# Baseboard_XIAO.net
KiCad netlist of a schematic drawn in EAGLE
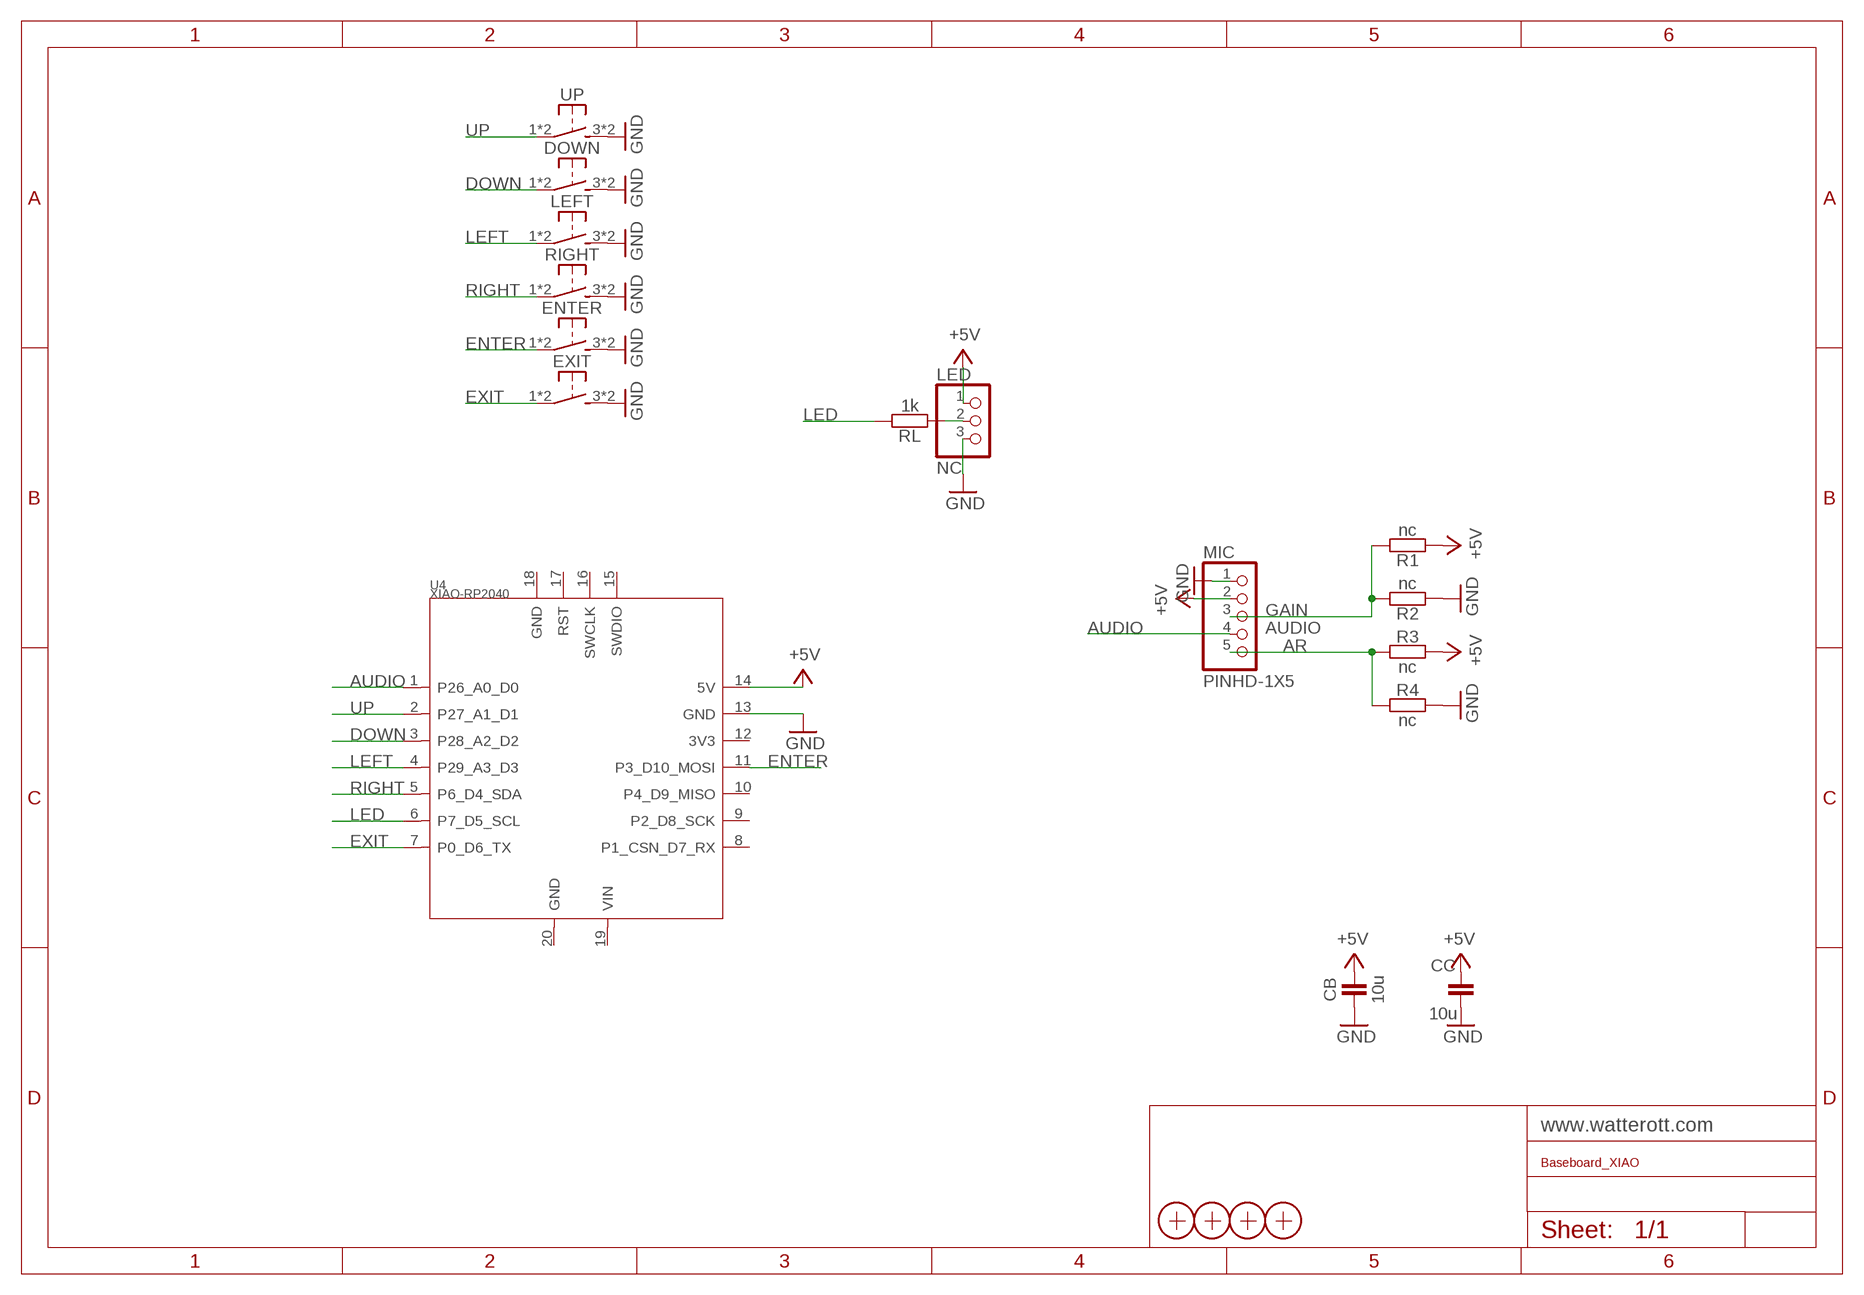
[diagram p0: schematic, sheet 1]

(export (version "E")
  (design (tool "Eeschema 10.0.6"))
  (components
    (comp (ref "CB")
      (value "10u")
      (footprint "eagle-import:C0603")
      (libsource (lib "eagle-import") (part "CAPACITOR-0603"))
    )
    (comp (ref "CC")
      (value "10u")
      (footprint "eagle-import:C0603")
      (libsource (lib "eagle-import") (part "CAPACITOR-0603"))
    )
    (comp (ref "DOWN")
      (value "SW-TACTILELSH")
      (footprint "eagle-import:SW6XG_LSH")
      (libsource (lib "eagle-import") (part "SW-TACTILELSH"))
    )
    (comp (ref "ENTER")
      (value "SW-TACTILELSH")
      (footprint "eagle-import:SW6XG_LSH")
      (libsource (lib "eagle-import") (part "SW-TACTILELSH"))
    )
    (comp (ref "EXIT")
      (value "SW-TACTILELSH")
      (footprint "eagle-import:SW6XG_LSH")
      (libsource (lib "eagle-import") (part "SW-TACTILELSH"))
    )
    (comp (ref "LED")
      (value "NC")
      (footprint "eagle-import:1X03")
      (libsource (lib "eagle-import") (part "PINHD-1X3"))
    )
    (comp (ref "LEFT")
      (value "SW-TACTILELSH")
      (footprint "eagle-import:SW6XG_LSH")
      (libsource (lib "eagle-import") (part "SW-TACTILELSH"))
    )
    (comp (ref "MIC")
      (value "PINHD-1X5")
      (footprint "eagle-import:1X05")
      (libsource (lib "eagle-import") (part "PINHD-1X5"))
    )
    (comp (ref "R1")
      (value "nc")
      (footprint "eagle-import:C0603")
      (libsource (lib "eagle-import") (part "RESISTOR-0603"))
    )
    (comp (ref "R2")
      (value "nc")
      (footprint "eagle-import:C0603")
      (libsource (lib "eagle-import") (part "RESISTOR-0603"))
    )
    (comp (ref "R3")
      (value "nc")
      (footprint "eagle-import:C0603")
      (libsource (lib "eagle-import") (part "RESISTOR-0603"))
    )
    (comp (ref "R4")
      (value "nc")
      (footprint "eagle-import:C0603")
      (libsource (lib "eagle-import") (part "RESISTOR-0603"))
    )
    (comp (ref "RIGHT")
      (value "SW-TACTILELSH")
      (footprint "eagle-import:SW6XG_LSH")
      (libsource (lib "eagle-import") (part "SW-TACTILELSH"))
    )
    (comp (ref "RL")
      (value "1k")
      (footprint "eagle-import:C0603")
      (libsource (lib "eagle-import") (part "RESISTOR-0603"))
    )
    (comp (ref "U4")
      (value "XIAO-RP2040")
      (footprint "eagle-import:XIAO-SAMD21_RP2040-MODULE14P-2.54-21X17.8MM")
      (libsource (lib "eagle-import") (part "XIAO-RP2040"))
    )
    (comp (ref "UP")
      (value "SW-TACTILELSH")
      (footprint "eagle-import:SW6XG_LSH")
      (libsource (lib "eagle-import") (part "SW-TACTILELSH"))
    )
    (comp (ref "X1")
      (value "PASSER-07")
      (footprint "eagle-import:PASSER_07MM")
      (libsource (lib "eagle-import") (part "PASSER-07"))
    )
    (comp (ref "X2")
      (value "PASSER-07")
      (footprint "eagle-import:PASSER_07MM")
      (libsource (lib "eagle-import") (part "PASSER-07"))
    )
    (comp (ref "X3")
      (value "PASSER-07")
      (footprint "eagle-import:PASSER_07MM")
      (libsource (lib "eagle-import") (part "PASSER-07"))
    )
    (comp (ref "X4")
      (value "PASSER-07")
      (footprint "eagle-import:PASSER_07MM")
      (libsource (lib "eagle-import") (part "PASSER-07"))
    )
  )
  (nets
    (net (code "1") (name "+5V") (class "Default")
      (node (ref "CB") (pin "2") (pinfunction "2_2") (pintype "passive"))
      (node (ref "CC") (pin "2") (pinfunction "2_2") (pintype "passive"))
      (node (ref "LED") (pin "1") (pinfunction "1_1") (pintype "passive"))
      (node (ref "MIC") (pin "2") (pinfunction "2_2") (pintype "passive"))
      (node (ref "R1") (pin "1") (pinfunction "1_1") (pintype "passive"))
      (node (ref "R3") (pin "2") (pinfunction "2_2") (pintype "passive"))
      (node (ref "U4") (pin "14") (pinfunction "5V_14") (pintype "bidirectional"))
    )
    (net (code "2") (name "/AR") (class "Default")
      (node (ref "MIC") (pin "5") (pinfunction "5_5") (pintype "passive"))
      (node (ref "R3") (pin "1") (pinfunction "1_1") (pintype "passive"))
      (node (ref "R4") (pin "1") (pinfunction "1_1") (pintype "passive"))
    )
    (net (code "3") (name "/AUDIO") (class "Default")
      (node (ref "MIC") (pin "4") (pinfunction "4_4") (pintype "passive"))
      (node (ref "U4") (pin "1") (pinfunction "P26_A0_D0_1") (pintype "bidirectional"))
    )
    (net (code "4") (name "/DOWN") (class "Default")
      (node (ref "DOWN") (pin "1") (pinfunction "P1_1") (pintype "passive"))
      (node (ref "DOWN") (pin "2") (pinfunction "P1_2") (pintype "passive"))
      (node (ref "U4") (pin "3") (pinfunction "P28_A2_D2_3") (pintype "bidirectional"))
    )
    (net (code "5") (name "/ENTER") (class "Default")
      (node (ref "ENTER") (pin "1") (pinfunction "P1_1") (pintype "passive"))
      (node (ref "ENTER") (pin "2") (pinfunction "P1_2") (pintype "passive"))
      (node (ref "U4") (pin "11") (pinfunction "P3_D10_MOSI_11") (pintype "bidirectional"))
    )
    (net (code "6") (name "/EXIT") (class "Default")
      (node (ref "EXIT") (pin "1") (pinfunction "P1_1") (pintype "passive"))
      (node (ref "EXIT") (pin "2") (pinfunction "P1_2") (pintype "passive"))
      (node (ref "U4") (pin "7") (pinfunction "P0_D6_TX_7") (pintype "bidirectional"))
    )
    (net (code "7") (name "/GAIN") (class "Default")
      (node (ref "MIC") (pin "3") (pinfunction "3_3") (pintype "passive"))
      (node (ref "R1") (pin "2") (pinfunction "2_2") (pintype "passive"))
      (node (ref "R2") (pin "2") (pinfunction "2_2") (pintype "passive"))
    )
    (net (code "8") (name "/LED") (class "Default")
      (node (ref "RL") (pin "2") (pinfunction "2_2") (pintype "passive"))
      (node (ref "U4") (pin "6") (pinfunction "P7_D5_SCL_6") (pintype "bidirectional"))
    )
    (net (code "9") (name "/LEFT") (class "Default")
      (node (ref "LEFT") (pin "1") (pinfunction "P1_1") (pintype "passive"))
      (node (ref "LEFT") (pin "2") (pinfunction "P1_2") (pintype "passive"))
      (node (ref "U4") (pin "4") (pinfunction "P29_A3_D3_4") (pintype "bidirectional"))
    )
    (net (code "10") (name "/RIGHT") (class "Default")
      (node (ref "RIGHT") (pin "1") (pinfunction "P1_1") (pintype "passive"))
      (node (ref "RIGHT") (pin "2") (pinfunction "P1_2") (pintype "passive"))
      (node (ref "U4") (pin "5") (pinfunction "P6_D4_SDA_5") (pintype "bidirectional"))
    )
    (net (code "11") (name "/UP") (class "Default")
      (node (ref "U4") (pin "2") (pinfunction "P27_A1_D1_2") (pintype "bidirectional"))
      (node (ref "UP") (pin "1") (pinfunction "P1_1") (pintype "passive"))
      (node (ref "UP") (pin "2") (pinfunction "P1_2") (pintype "passive"))
    )
    (net (code "12") (name "GND") (class "Default")
      (node (ref "CB") (pin "1") (pinfunction "1_1") (pintype "passive"))
      (node (ref "CC") (pin "1") (pinfunction "1_1") (pintype "passive"))
      (node (ref "DOWN") (pin "3") (pinfunction "S1_3") (pintype "passive"))
      (node (ref "DOWN") (pin "4") (pinfunction "S1_4") (pintype "passive"))
      (node (ref "ENTER") (pin "3") (pinfunction "S1_3") (pintype "passive"))
      (node (ref "ENTER") (pin "4") (pinfunction "S1_4") (pintype "passive"))
      (node (ref "EXIT") (pin "3") (pinfunction "S1_3") (pintype "passive"))
      (node (ref "EXIT") (pin "4") (pinfunction "S1_4") (pintype "passive"))
      (node (ref "LED") (pin "3") (pinfunction "3_3") (pintype "passive"))
      (node (ref "LEFT") (pin "3") (pinfunction "S1_3") (pintype "passive"))
      (node (ref "LEFT") (pin "4") (pinfunction "S1_4") (pintype "passive"))
      (node (ref "MIC") (pin "1") (pinfunction "1_1") (pintype "passive"))
      (node (ref "R2") (pin "1") (pinfunction "1_1") (pintype "passive"))
      (node (ref "R4") (pin "2") (pinfunction "2_2") (pintype "passive"))
      (node (ref "RIGHT") (pin "3") (pinfunction "S1_3") (pintype "passive"))
      (node (ref "RIGHT") (pin "4") (pinfunction "S1_4") (pintype "passive"))
      (node (ref "U4") (pin "13") (pinfunction "GND_13") (pintype "bidirectional"))
      (node (ref "UP") (pin "3") (pinfunction "S1_3") (pintype "passive"))
      (node (ref "UP") (pin "4") (pinfunction "S1_4") (pintype "passive"))
    )
    (net (code "13") (name "Net-(LED-Pad2)") (class "Default")
      (node (ref "LED") (pin "2") (pinfunction "2_2") (pintype "passive"))
      (node (ref "RL") (pin "1") (pinfunction "1_1") (pintype "passive"))
    )
    (net (code "14") (name "unconnected-(U4-3V3-Pad12)") (class "Default")
      (node (ref "U4") (pin "12") (pinfunction "3V3_12") (pintype "bidirectional"))
    )
    (net (code "15") (name "unconnected-(U4-GND-Pad18)") (class "Default")
      (node (ref "U4") (pin "18") (pinfunction "GND_18") (pintype "bidirectional"))
    )
    (net (code "16") (name "unconnected-(U4-GND-Pad20)") (class "Default")
      (node (ref "U4") (pin "20") (pinfunction "GND_20") (pintype "bidirectional"))
    )
    (net (code "17") (name "unconnected-(U4-P1_CSN_D7_RX-Pad8)") (class "Default")
      (node (ref "U4") (pin "8") (pinfunction "P1_CSN_D7_RX_8") (pintype "bidirectional"))
    )
    (net (code "18") (name "unconnected-(U4-P2_D8_SCK-Pad9)") (class "Default")
      (node (ref "U4") (pin "9") (pinfunction "P2_D8_SCK_9") (pintype "bidirectional"))
    )
    (net (code "19") (name "unconnected-(U4-P4_D9_MISO-Pad10)") (class "Default")
      (node (ref "U4") (pin "10") (pinfunction "P4_D9_MISO_10") (pintype "bidirectional"))
    )
    (net (code "20") (name "unconnected-(U4-RST-Pad17)") (class "Default")
      (node (ref "U4") (pin "17") (pinfunction "RST_17") (pintype "bidirectional"))
    )
    (net (code "21") (name "unconnected-(U4-SWCLK-Pad16)") (class "Default")
      (node (ref "U4") (pin "16") (pinfunction "SWCLK_16") (pintype "bidirectional"))
    )
    (net (code "22") (name "unconnected-(U4-SWDIO-Pad15)") (class "Default")
      (node (ref "U4") (pin "15") (pinfunction "SWDIO_15") (pintype "bidirectional"))
    )
    (net (code "23") (name "unconnected-(U4-VIN-Pad19)") (class "Default")
      (node (ref "U4") (pin "19") (pinfunction "VIN_19") (pintype "bidirectional"))
    )
  )
)
